# Master.net
KiCad netlist of a schematic drawn in Altium Designer
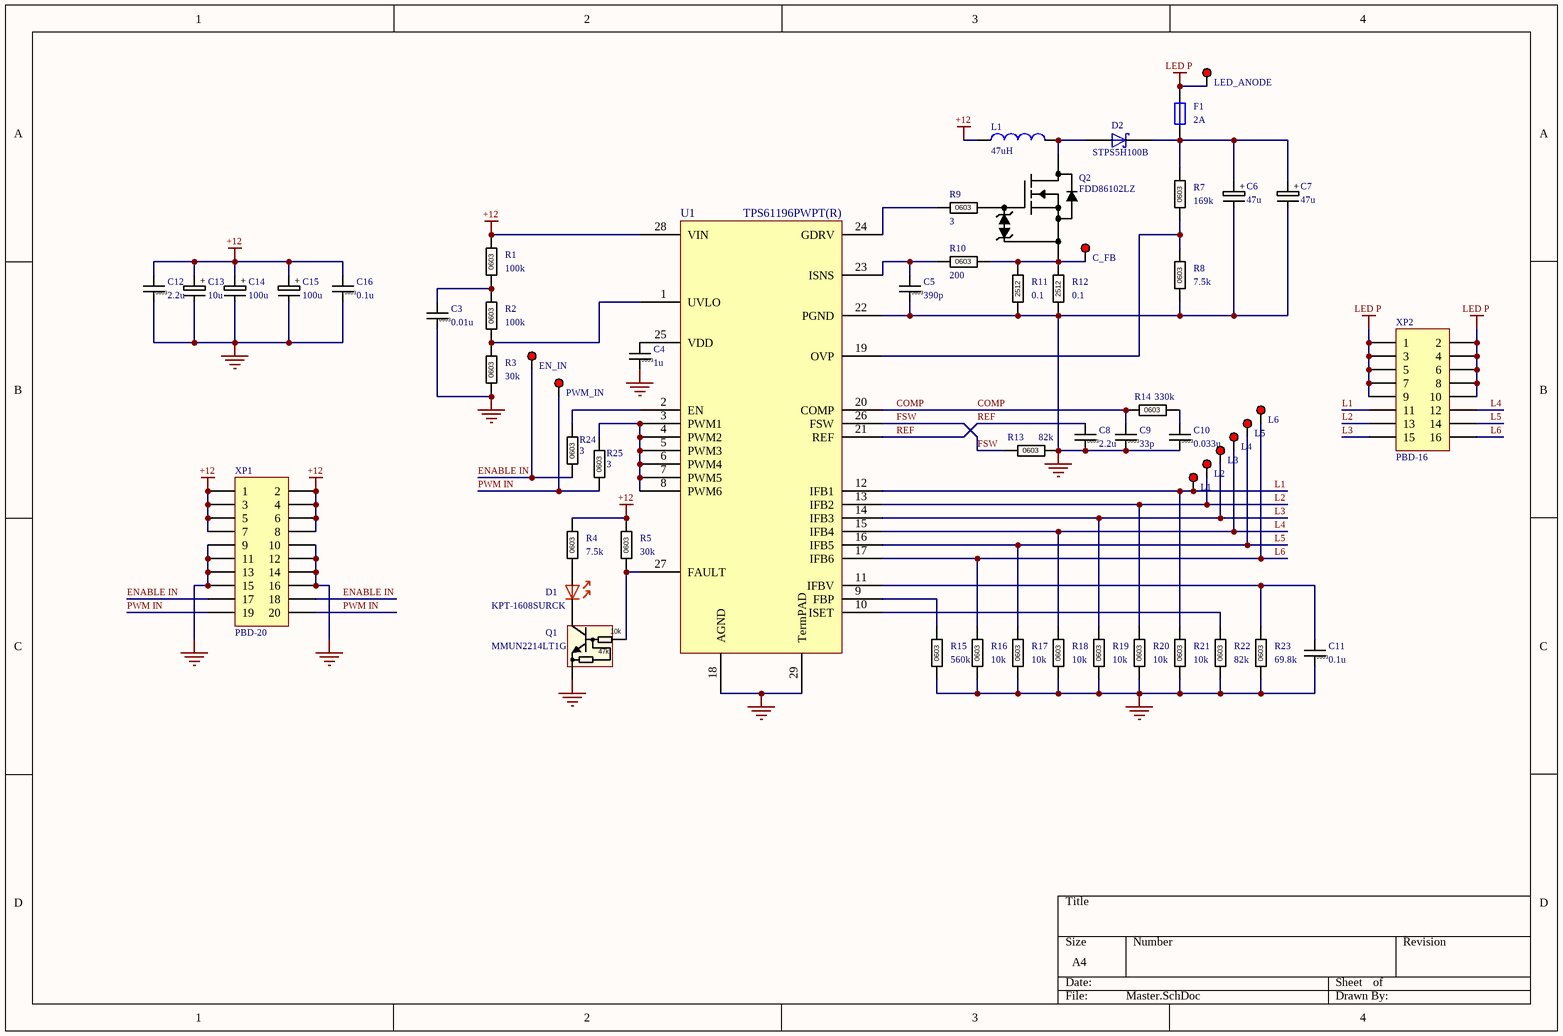
[diagram p0: Master.SchDoc]

(export (version "E")
  (design (tool "Eeschema 10.0.6"))
  (components
    (comp (ref "C3")
      (value "0603-X7R-50-0.01 мкф")
      (footprint "CAP_0603")
      (description "Конденсатор Чип Керамический")
      (fields (field (name "VOLTAGE") "50V") (field (name "CAP") "0.01u") (field (name "FOOT") "0603"))
      (libsource (lib "main") (part "0603-X7R-50-0.01 мкф"))
    )
    (comp (ref "C4")
      (value "0603-X5R-10 1 мкф")
      (footprint "CAP_0603")
      (description "Конденсатор Чип Керамический")
      (fields (field (name "VOLTAGE") "10V") (field (name "CAP") "1u") (field (name "FOOT") "0603"))
      (libsource (lib "main") (part "0603-X5R-10 1 мкф"))
    )
    (comp (ref "C5")
      (value "0603-NP0-50-390 пф J")
      (footprint "CAP_0603")
      (description "Конденсатор Чип Керамический")
      (fields (field (name "VOLTAGE") "50V") (field (name "CAP") "390p") (field (name "FOOT") "0603"))
      (libsource (lib "main") (part "0603-NP0-50-390 пф J"))
    )
    (comp (ref "C6")
      (value "ECAP 47uF 100V 10x12.5")
      (footprint "CAP_ECR 10X12.5")
      (fields (field (name "VOLTAGE") "100V") (field (name "CAP") "47u"))
      (libsource (lib "main") (part "ECAP 47uF 100V 10x12.5"))
    )
    (comp (ref "C7")
      (value "ECAP 47uF 100V 10x12.5")
      (footprint "CAP_ECR 10X12.5")
      (fields (field (name "VOLTAGE") "100V") (field (name "CAP") "47u"))
      (libsource (lib "main") (part "ECAP 47uF 100V 10x12.5"))
    )
    (comp (ref "C8")
      (value "0603-X7R-10 2.2 мкф")
      (footprint "CAP_0603")
      (description "Конденсатор Чип Керамический")
      (fields (field (name "VOLTAGE") "10V") (field (name "CAP") "2.2u") (field (name "FOOT") "0603"))
      (libsource (lib "main") (part "0603-X7R-10 2.2 мкф"))
    )
    (comp (ref "C9")
      (value "0603-NP0-50-33 пф J")
      (footprint "CAP_0603")
      (description "Конденсатор Чип Керамический")
      (fields (field (name "VOLTAGE") "50V") (field (name "CAP") "33p") (field (name "FOOT") "0603"))
      (libsource (lib "main") (part "0603-NP0-50-33 пф J"))
    )
    (comp (ref "C10")
      (value "0603-X7R-50-0.033 мкф")
      (footprint "CAP_0603")
      (description "Конденсатор Чип Керамический")
      (fields (field (name "VOLTAGE") "50V") (field (name "CAP") "0.033u") (field (name "FOOT") "0603"))
      (libsource (lib "main") (part "0603-X7R-50-0.033 мкф"))
    )
    (comp (ref "C11")
      (value "0603-X7R-50-0.1 мкф")
      (footprint "CAP_0603")
      (description "Конденсатор Чип Керамический")
      (fields (field (name "VOLTAGE") "50V") (field (name "CAP") "0.1u") (field (name "FOOT") "0603"))
      (libsource (lib "main") (part "0603-X7R-50-0.1 мкф"))
    )
    (comp (ref "C12")
      (value "0603-X7R-10 2.2 мкф")
      (footprint "CAP_0603")
      (description "Конденсатор Чип Керамический")
      (fields (field (name "VOLTAGE") "10V") (field (name "CAP") "2.2u") (field (name "FOOT") "0603"))
      (libsource (lib "main") (part "0603-X7R-10 2.2 мкф"))
    )
    (comp (ref "C13")
      (value "ESX 50 в-10 мкф 5x11 Hitano")
      (footprint "CAP_ECR 5X11")
      (description "Конденсатор Алюминиевый Низкоимпедансный")
      (fields (field (name "VOLTAGE") "50V") (field (name "CAP") "10u"))
      (libsource (lib "main") (part "ESX 50 в-10 мкф 5x11 Hitano"))
    )
    (comp (ref "C14")
      (value "ECAP (К50-35), 100мкФ, 35В, 105°C, 20%, 6.3x12мм P:2.5мм")
      (footprint "CAP_ECR 5X11")
      (description "Конденсатор электролитический алюминиевый")
      (fields (field (name "VOLTAGE") "50V") (field (name "CAP") "100u"))
      (libsource (lib "main") (part "ECAP 50V 100uF 6.3x12"))
    )
    (comp (ref "C15")
      (value "ECAP (К50-35), 100мкФ, 35В, 105°C, 20%, 6.3x12мм P:2.5мм")
      (footprint "CAP_ECR 5X11")
      (description "Конденсатор электролитический алюминиевый")
      (fields (field (name "VOLTAGE") "50V") (field (name "CAP") "100u"))
      (libsource (lib "main") (part "ECAP 50V 100uF 6.3x12"))
    )
    (comp (ref "C16")
      (value "0603-X7R-50-0.1 мкф")
      (footprint "CAP_0603")
      (description "Конденсатор Чип Керамический")
      (fields (field (name "VOLTAGE") "50V") (field (name "CAP") "0.1u") (field (name "FOOT") "0603"))
      (libsource (lib "main") (part "0603-X7R-50-0.1 мкф"))
    )
    (comp (ref "D1")
      (value "KPT-1608SURCK")
      (footprint "LED_0603_RED")
      (fields
        (field (name "Comment") "KPT-1608SURCK, KingBright")
        (field (name "HELPURL") "L:\\Dev\\Техническая документация\\Светодиоды\\Kingbright\\SMD\\KPT-1608SURCK(0603).pdf")
      )
      (libsource (lib "main") (part "LED_0603_KPT-1608SURCK_red_120mcd"))
    )
    (comp (ref "D2")
      (value "STPS5H100B")
      (footprint "D-PAK")
      (description "DIODE SCHOTTKY 5A 100V")
      (libsource (lib "main") (part "Schottky_STPS5H100B"))
    )
    (comp (ref "F1")
      (value "2A")
      (footprint "FUSE_LITTEL_0154")
      (description "Плавкий предохранитель LITTELFUSE 0154")
      (libsource (lib "main") (part "FUSE_LITTEL 0154"))
    )
    (comp (ref "L1")
      (value "47uH")
      (footprint "INDUCTOR_B82477G")
      (description "47 мкГн, 2.5 А, 12.8х12.8, Катушка индуктивности SMD")
      (libsource (lib "main") (part "INDUCTOR_B82477G4473M"))
    )
    (comp (ref "Q1")
      (value "MMUN2214LT1G")
      (footprint "SOT_23")
      (description "NPN Digital Transistor")
      (fields (field (name "PUBLISHER") "Altium Limited"))
      (libsource (lib "main") (part "BEC_MMUN2214LT1G_50V 0.1A 0.25W"))
    )
    (comp (ref "Q2")
      (value "FDD86102LZ")
      (footprint "D-PAK")
      (description "MOSFET N-CHANNEL 100V 8A")
      (libsource (lib "main") (part "MOSFET_FDD86102LZ"))
    )
    (comp (ref "R1")
      (value "100k")
      (footprint "resistor_0603")
      (description "Резистор Чип")
      (fields
        (field (name "POWER") "0.1W")
        (field (name "FOOT") "0603")
        (field (name "Comment") "0603-100к J")
      )
      (libsource (lib "main") (part "0603-100 к J"))
    )
    (comp (ref "R2")
      (value "100k")
      (footprint "resistor_0603")
      (description "Резистор Чип")
      (fields
        (field (name "POWER") "0.1W")
        (field (name "FOOT") "0603")
        (field (name "Comment") "0603-100к J")
      )
      (libsource (lib "main") (part "0603-100 к J"))
    )
    (comp (ref "R3")
      (value "30k")
      (footprint "resistor_0603")
      (description "Резистор Чип")
      (fields (field (name "POWER") "0.1W") (field (name "TOLERANCE") "1%") (field (name "FOOT") "0603"))
      (libsource (lib "main") (part "0603-30 к F"))
    )
    (comp (ref "R4")
      (value "7.5k")
      (footprint "resistor_0603")
      (description "Резистор Чип")
      (fields (field (name "POWER") "0.1W") (field (name "TOLERANCE") "1%") (field (name "FOOT") "0603"))
      (libsource (lib "main") (part "0603-7.5 к F"))
    )
    (comp (ref "R5")
      (value "30k")
      (footprint "resistor_0603")
      (description "Резистор Чип")
      (fields (field (name "POWER") "0.1W") (field (name "TOLERANCE") "1%") (field (name "FOOT") "0603"))
      (libsource (lib "main") (part "0603-30 к F"))
    )
    (comp (ref "R7")
      (value "169k")
      (footprint "resistor_0603")
      (description "Резистор Чип")
      (fields (field (name "POWER") "0.1W") (field (name "TOLERANCE") "1%") (field (name "FOOT") "0603"))
      (libsource (lib "main") (part "0603-169 к F"))
    )
    (comp (ref "R8")
      (value "7.5k")
      (footprint "resistor_0603")
      (description "Резистор Чип")
      (fields (field (name "POWER") "0.1W") (field (name "TOLERANCE") "1%") (field (name "FOOT") "0603"))
      (libsource (lib "main") (part "0603-7.5 к F"))
    )
    (comp (ref "R9")
      (value "3")
      (footprint "resistor_0603")
      (description "Резистор Чип")
      (fields (field (name "POWER") "0.1W") (field (name "TOLERANCE") "1%") (field (name "FOOT") "0603"))
      (libsource (lib "main") (part "0603-3 F"))
    )
    (comp (ref "R10")
      (value "200")
      (footprint "resistor_0603")
      (description "Резистор Чип")
      (fields (field (name "POWER") "0.1W") (field (name "TOLERANCE") "1%") (field (name "FOOT") "0603"))
      (libsource (lib "main") (part "0603-200 F"))
    )
    (comp (ref "R11")
      (value "0.1")
      (footprint "resistor_2512")
      (description "Резистор Чип")
      (fields (field (name "POWER") "1W") (field (name "FOOT") "2512") (field (name "Comment") "2512-0.1 F"))
      (libsource (lib "main") (part "2512-0.1 F"))
    )
    (comp (ref "R12")
      (value "0.1")
      (footprint "resistor_2512")
      (description "Резистор Чип")
      (fields (field (name "POWER") "1W") (field (name "FOOT") "2512") (field (name "Comment") "2512-0.1 F"))
      (libsource (lib "main") (part "2512-0.1 F"))
    )
    (comp (ref "R13")
      (value "82k")
      (footprint "resistor_0603")
      (description "Резистор Чип")
      (fields
        (field (name "POWER") "0.1W")
        (field (name "FOOT") "0603")
        (field (name "Comment") "0603-82 к J")
      )
      (libsource (lib "main") (part "0603-82 к J"))
    )
    (comp (ref "R14")
      (value "330k")
      (footprint "resistor_0603")
      (description "Резистор Чип")
      (fields
        (field (name "POWER") "0.1W")
        (field (name "FOOT") "0603")
        (field (name "Comment") "0603-330 J")
      )
      (libsource (lib "main") (part "0603-330 J"))
    )
    (comp (ref "R15")
      (value "560k")
      (footprint "resistor_0603")
      (description "Резистор Чип")
      (fields (field (name "POWER") "0.1W") (field (name "TOLERANCE") "1%") (field (name "FOOT") "0603"))
      (libsource (lib "main") (part "0603-560 к F"))
    )
    (comp (ref "R16")
      (value "10k")
      (footprint "resistor_0603")
      (description "Резистор Чип")
      (fields
        (field (name "POWER") "0.1W")
        (field (name "FOOT") "0603")
        (field (name "Comment") "0603-10к J")
      )
      (libsource (lib "main") (part "0603-10 к J"))
    )
    (comp (ref "R17")
      (value "10k")
      (footprint "resistor_0603")
      (description "Резистор Чип")
      (fields
        (field (name "POWER") "0.1W")
        (field (name "FOOT") "0603")
        (field (name "Comment") "0603-10к J")
      )
      (libsource (lib "main") (part "0603-10 к J"))
    )
    (comp (ref "R18")
      (value "10k")
      (footprint "resistor_0603")
      (description "Резистор Чип")
      (fields
        (field (name "POWER") "0.1W")
        (field (name "FOOT") "0603")
        (field (name "Comment") "0603-10к J")
      )
      (libsource (lib "main") (part "0603-10 к J"))
    )
    (comp (ref "R19")
      (value "10k")
      (footprint "resistor_0603")
      (description "Резистор Чип")
      (fields
        (field (name "POWER") "0.1W")
        (field (name "FOOT") "0603")
        (field (name "Comment") "0603-10к J")
      )
      (libsource (lib "main") (part "0603-10 к J"))
    )
    (comp (ref "R20")
      (value "10k")
      (footprint "resistor_0603")
      (description "Резистор Чип")
      (fields
        (field (name "POWER") "0.1W")
        (field (name "FOOT") "0603")
        (field (name "Comment") "0603-10к J")
      )
      (libsource (lib "main") (part "0603-10 к J"))
    )
    (comp (ref "R21")
      (value "10k")
      (footprint "resistor_0603")
      (description "Резистор Чип")
      (fields
        (field (name "POWER") "0.1W")
        (field (name "FOOT") "0603")
        (field (name "Comment") "0603-10к J")
      )
      (libsource (lib "main") (part "0603-10 к J"))
    )
    (comp (ref "R22")
      (value "82k")
      (footprint "resistor_0603")
      (description "Резистор Чип")
      (fields
        (field (name "POWER") "0.1W")
        (field (name "FOOT") "0603")
        (field (name "Comment") "0603-82 к J")
      )
      (libsource (lib "main") (part "0603-82 к J"))
    )
    (comp (ref "R23")
      (value "69.8k")
      (footprint "resistor_0603")
      (description "Резистор Чип")
      (fields (field (name "POWER") "0.1W") (field (name "TOLERANCE") "1%") (field (name "FOOT") "0603"))
      (libsource (lib "main") (part "0603-69.8 к F"))
    )
    (comp (ref "R24")
      (value "3")
      (footprint "resistor_0603")
      (description "Резистор Чип")
      (fields (field (name "POWER") "0.1W") (field (name "TOLERANCE") "1%") (field (name "FOOT") "0603"))
      (libsource (lib "main") (part "0603-3 F"))
    )
    (comp (ref "R25")
      (value "3")
      (footprint "resistor_0603")
      (description "Резистор Чип")
      (fields (field (name "POWER") "0.1W") (field (name "TOLERANCE") "1%") (field (name "FOOT") "0603"))
      (libsource (lib "main") (part "0603-3 F"))
    )
    (comp (ref "TP1")
      (value "LED_ANODE")
      (footprint "OTHER_SMD_TP_1.5MM")
      (libsource (lib "main") (part "Test Point_1.5MM"))
    )
    (comp (ref "TP2")
      (value "EN_IN")
      (footprint "OTHER_SMD_TP_1.5MM")
      (libsource (lib "main") (part "Test Point_1.5MM"))
    )
    (comp (ref "TP3")
      (value "PWM_IN")
      (footprint "OTHER_SMD_TP_1.5MM")
      (libsource (lib "main") (part "Test Point_1.5MM"))
    )
    (comp (ref "TP4")
      (value "L1")
      (footprint "OTHER_SMD_TP_1.5MM")
      (libsource (lib "main") (part "Test Point_1.5MM"))
    )
    (comp (ref "TP5")
      (value "L2")
      (footprint "OTHER_SMD_TP_1.5MM")
      (libsource (lib "main") (part "Test Point_1.5MM"))
    )
    (comp (ref "TP6")
      (value "L3")
      (footprint "OTHER_SMD_TP_1.5MM")
      (libsource (lib "main") (part "Test Point_1.5MM"))
    )
    (comp (ref "TP7")
      (value "L4")
      (footprint "OTHER_SMD_TP_1.5MM")
      (libsource (lib "main") (part "Test Point_1.5MM"))
    )
    (comp (ref "TP8")
      (value "L5")
      (footprint "OTHER_SMD_TP_1.5MM")
      (libsource (lib "main") (part "Test Point_1.5MM"))
    )
    (comp (ref "TP9")
      (value "L6")
      (footprint "OTHER_SMD_TP_1.5MM")
      (libsource (lib "main") (part "Test Point_1.5MM"))
    )
    (comp (ref "TP10")
      (value "C_FB")
      (footprint "OTHER_SMD_TP_1.5MM")
      (libsource (lib "main") (part "Test Point_1.5MM"))
    )
    (comp (ref "U1")
      (value "TPS61196PWPT(R)")
      (footprint "HTSSOP_28")
      (libsource (lib "main") (part "LED DRV_TPS61196"))
    )
    (comp (ref "XP1")
      (value "PBD-20")
      (footprint "CONN_PBD-20")
      (description "Header, 10-Pin, Dual row")
      (fields (field (name "PUBLISHER") "Altium Limited"))
      (libsource (lib "main") (part "CONN_PBD-20"))
    )
    (comp (ref "XP2")
      (value "PBD-16")
      (footprint "CONN_PBD-16")
      (description "Header, 8-Pin, Dual row")
      (fields (field (name "PUBLISHER") "Altium Limited"))
      (libsource (lib "main") (part "CONN_PBD-16"))
    )
  )
  (nets
    (net (code "1") (name "+12") (class "Default")
      (node (ref "C12") (pin "1") (pinfunction "1_1") (pintype "passive"))
      (node (ref "C13") (pin "1") (pinfunction "1_1") (pintype "passive"))
      (node (ref "C14") (pin "1") (pinfunction "1_1") (pintype "passive"))
      (node (ref "C15") (pin "1") (pinfunction "1_1") (pintype "passive"))
      (node (ref "C16") (pin "1") (pinfunction "1_1") (pintype "passive"))
      (node (ref "L1") (pin "1") (pinfunction "1_1") (pintype "passive"))
      (node (ref "R1") (pin "2") (pinfunction "2_2") (pintype "passive"))
      (node (ref "R4") (pin "2") (pinfunction "2_2") (pintype "passive"))
      (node (ref "R5") (pin "2") (pinfunction "2_2") (pintype "passive"))
      (node (ref "U1") (pin "28") (pinfunction "VIN_28") (pintype "passive"))
      (node (ref "XP1") (pin "1") (pinfunction "1_1") (pintype "passive"))
      (node (ref "XP1") (pin "2") (pinfunction "2_2") (pintype "passive"))
      (node (ref "XP1") (pin "3") (pinfunction "3_3") (pintype "passive"))
      (node (ref "XP1") (pin "4") (pinfunction "4_4") (pintype "passive"))
      (node (ref "XP1") (pin "5") (pinfunction "5_5") (pintype "passive"))
      (node (ref "XP1") (pin "6") (pinfunction "6_6") (pintype "passive"))
      (node (ref "XP1") (pin "7") (pinfunction "7_7") (pintype "passive"))
      (node (ref "XP1") (pin "8") (pinfunction "8_8") (pintype "passive"))
    )
    (net (code "2") (name "/COMP") (class "Default")
      (node (ref "C9") (pin "1") (pinfunction "1_1") (pintype "passive"))
      (node (ref "R14") (pin "2") (pinfunction "2_2") (pintype "passive"))
      (node (ref "U1") (pin "20") (pinfunction "COMP_20") (pintype "passive"))
    )
    (net (code "3") (name "/ENABLE IN") (class "Default")
      (node (ref "R24") (pin "1") (pinfunction "1_1") (pintype "passive"))
      (node (ref "TP2") (pin "1") (pinfunction "1_1") (pintype "passive"))
      (node (ref "XP1") (pin "17") (pinfunction "17_17") (pintype "passive"))
      (node (ref "XP1") (pin "18") (pinfunction "18_18") (pintype "passive"))
    )
    (net (code "4") (name "/FSW") (class "Default")
      (node (ref "R13") (pin "1") (pinfunction "1_1") (pintype "passive"))
      (node (ref "U1") (pin "26") (pinfunction "FSW_26") (pintype "passive"))
    )
    (net (code "5") (name "/L1") (class "Default")
      (node (ref "R21") (pin "2") (pinfunction "2_2") (pintype "passive"))
      (node (ref "TP4") (pin "1") (pinfunction "1_1") (pintype "passive"))
      (node (ref "U1") (pin "12") (pinfunction "IFB1_12") (pintype "passive"))
      (node (ref "XP2") (pin "11") (pinfunction "11_11") (pintype "passive"))
    )
    (net (code "6") (name "/L2") (class "Default")
      (node (ref "R20") (pin "2") (pinfunction "2_2") (pintype "passive"))
      (node (ref "TP5") (pin "1") (pinfunction "1_1") (pintype "passive"))
      (node (ref "U1") (pin "13") (pinfunction "IFB2_13") (pintype "passive"))
      (node (ref "XP2") (pin "13") (pinfunction "13_13") (pintype "passive"))
    )
    (net (code "7") (name "/L3") (class "Default")
      (node (ref "R19") (pin "2") (pinfunction "2_2") (pintype "passive"))
      (node (ref "TP6") (pin "1") (pinfunction "1_1") (pintype "passive"))
      (node (ref "U1") (pin "14") (pinfunction "IFB3_14") (pintype "passive"))
      (node (ref "XP2") (pin "15") (pinfunction "15_15") (pintype "passive"))
    )
    (net (code "8") (name "/L4") (class "Default")
      (node (ref "R18") (pin "2") (pinfunction "2_2") (pintype "passive"))
      (node (ref "TP7") (pin "1") (pinfunction "1_1") (pintype "passive"))
      (node (ref "U1") (pin "15") (pinfunction "IFB4_15") (pintype "passive"))
      (node (ref "XP2") (pin "12") (pinfunction "12_12") (pintype "passive"))
    )
    (net (code "9") (name "/L5") (class "Default")
      (node (ref "R17") (pin "2") (pinfunction "2_2") (pintype "passive"))
      (node (ref "TP8") (pin "1") (pinfunction "1_1") (pintype "passive"))
      (node (ref "U1") (pin "16") (pinfunction "IFB5_16") (pintype "passive"))
      (node (ref "XP2") (pin "14") (pinfunction "14_14") (pintype "passive"))
    )
    (net (code "10") (name "/L6") (class "Default")
      (node (ref "R16") (pin "2") (pinfunction "2_2") (pintype "passive"))
      (node (ref "TP9") (pin "1") (pinfunction "1_1") (pintype "passive"))
      (node (ref "U1") (pin "17") (pinfunction "IFB6_17") (pintype "passive"))
      (node (ref "XP2") (pin "16") (pinfunction "16_16") (pintype "passive"))
    )
    (net (code "11") (name "/PWM IN") (class "Default")
      (node (ref "R25") (pin "1") (pinfunction "1_1") (pintype "passive"))
      (node (ref "TP3") (pin "1") (pinfunction "1_1") (pintype "passive"))
      (node (ref "XP1") (pin "19") (pinfunction "19_19") (pintype "passive"))
      (node (ref "XP1") (pin "20") (pinfunction "20_20") (pintype "passive"))
    )
    (net (code "12") (name "/REF") (class "Default")
      (node (ref "C8") (pin "1") (pinfunction "1_1") (pintype "passive"))
      (node (ref "U1") (pin "21") (pinfunction "REF_21") (pintype "passive"))
    )
    (net (code "13") (name "GND") (class "Default")
      (node (ref "C10") (pin "2") (pinfunction "2_2") (pintype "passive"))
      (node (ref "C11") (pin "2") (pinfunction "2_2") (pintype "passive"))
      (node (ref "C12") (pin "2") (pinfunction "2_2") (pintype "passive"))
      (node (ref "C13") (pin "2") (pinfunction "2_2") (pintype "passive"))
      (node (ref "C14") (pin "2") (pinfunction "2_2") (pintype "passive"))
      (node (ref "C15") (pin "2") (pinfunction "2_2") (pintype "passive"))
      (node (ref "C16") (pin "2") (pinfunction "2_2") (pintype "passive"))
      (node (ref "C3") (pin "2") (pinfunction "2_2") (pintype "passive"))
      (node (ref "C4") (pin "2") (pinfunction "2_2") (pintype "passive"))
      (node (ref "C5") (pin "2") (pinfunction "2_2") (pintype "passive"))
      (node (ref "C6") (pin "2") (pinfunction "2_2") (pintype "passive"))
      (node (ref "C7") (pin "2") (pinfunction "2_2") (pintype "passive"))
      (node (ref "C8") (pin "2") (pinfunction "2_2") (pintype "passive"))
      (node (ref "C9") (pin "2") (pinfunction "2_2") (pintype "passive"))
      (node (ref "Q1") (pin "2") (pinfunction "E_2") (pintype "passive"))
      (node (ref "R11") (pin "1") (pinfunction "1_1") (pintype "passive"))
      (node (ref "R12") (pin "1") (pinfunction "1_1") (pintype "passive"))
      (node (ref "R13") (pin "2") (pinfunction "2_2") (pintype "passive"))
      (node (ref "R15") (pin "1") (pinfunction "1_1") (pintype "passive"))
      (node (ref "R16") (pin "1") (pinfunction "1_1") (pintype "passive"))
      (node (ref "R17") (pin "1") (pinfunction "1_1") (pintype "passive"))
      (node (ref "R18") (pin "1") (pinfunction "1_1") (pintype "passive"))
      (node (ref "R19") (pin "1") (pinfunction "1_1") (pintype "passive"))
      (node (ref "R20") (pin "1") (pinfunction "1_1") (pintype "passive"))
      (node (ref "R21") (pin "1") (pinfunction "1_1") (pintype "passive"))
      (node (ref "R22") (pin "1") (pinfunction "1_1") (pintype "passive"))
      (node (ref "R23") (pin "1") (pinfunction "1_1") (pintype "passive"))
      (node (ref "R3") (pin "1") (pinfunction "1_1") (pintype "passive"))
      (node (ref "R8") (pin "1") (pinfunction "1_1") (pintype "passive"))
      (node (ref "U1") (pin "18") (pinfunction "AGND_18") (pintype "passive"))
      (node (ref "U1") (pin "22") (pinfunction "PGND_22") (pintype "passive"))
      (node (ref "U1") (pin "29") (pinfunction "TermPAD_29") (pintype "passive"))
      (node (ref "XP1") (pin "10") (pinfunction "10_10") (pintype "passive"))
      (node (ref "XP1") (pin "11") (pinfunction "11_11") (pintype "passive"))
      (node (ref "XP1") (pin "12") (pinfunction "12_12") (pintype "passive"))
      (node (ref "XP1") (pin "13") (pinfunction "13_13") (pintype "passive"))
      (node (ref "XP1") (pin "14") (pinfunction "14_14") (pintype "passive"))
      (node (ref "XP1") (pin "15") (pinfunction "15_15") (pintype "passive"))
      (node (ref "XP1") (pin "16") (pinfunction "16_16") (pintype "passive"))
      (node (ref "XP1") (pin "9") (pinfunction "9_9") (pintype "passive"))
    )
    (net (code "14") (name "LED P") (class "Default")
      (node (ref "F1") (pin "2") (pinfunction "2_2") (pintype "passive"))
      (node (ref "TP1") (pin "1") (pinfunction "1_1") (pintype "passive"))
      (node (ref "XP2") (pin "1") (pinfunction "1_1") (pintype "passive"))
      (node (ref "XP2") (pin "10") (pinfunction "10_10") (pintype "passive"))
      (node (ref "XP2") (pin "2") (pinfunction "2_2") (pintype "passive"))
      (node (ref "XP2") (pin "3") (pinfunction "3_3") (pintype "passive"))
      (node (ref "XP2") (pin "4") (pinfunction "4_4") (pintype "passive"))
      (node (ref "XP2") (pin "5") (pinfunction "5_5") (pintype "passive"))
      (node (ref "XP2") (pin "6") (pinfunction "6_6") (pintype "passive"))
      (node (ref "XP2") (pin "7") (pinfunction "7_7") (pintype "passive"))
      (node (ref "XP2") (pin "8") (pinfunction "8_8") (pintype "passive"))
      (node (ref "XP2") (pin "9") (pinfunction "9_9") (pintype "passive"))
    )
    (net (code "15") (name "Net-(C3-Pad1)") (class "Default")
      (node (ref "C3") (pin "1") (pinfunction "1_1") (pintype "passive"))
      (node (ref "R1") (pin "1") (pinfunction "1_1") (pintype "passive"))
      (node (ref "R2") (pin "2") (pinfunction "2_2") (pintype "passive"))
    )
    (net (code "16") (name "Net-(C10-Pad1)") (class "Default")
      (node (ref "C10") (pin "1") (pinfunction "1_1") (pintype "passive"))
      (node (ref "R14") (pin "1") (pinfunction "1_1") (pintype "passive"))
    )
    (net (code "17") (name "Net-(D1-Pad1)") (class "Default")
      (node (ref "D1") (pin "1") (pinfunction "1_1") (pintype "passive"))
      (node (ref "R4") (pin "1") (pinfunction "1_1") (pintype "passive"))
    )
    (net (code "18") (name "Net-(D2-A)") (class "Default")
      (node (ref "D2") (pin "2") (pinfunction "A_2") (pintype "passive"))
      (node (ref "L1") (pin "2") (pinfunction "2_2") (pintype "passive"))
      (node (ref "Q2") (pin "3") (pinfunction "D_3") (pintype "passive"))
    )
    (net (code "19") (name "Net-(D2-K)") (class "Default")
      (node (ref "C6") (pin "1") (pinfunction "1_1") (pintype "passive"))
      (node (ref "C7") (pin "1") (pinfunction "1_1") (pintype "passive"))
      (node (ref "D2") (pin "3") (pinfunction "K_3") (pintype "passive"))
      (node (ref "F1") (pin "1") (pinfunction "1_1") (pintype "passive"))
      (node (ref "R7") (pin "2") (pinfunction "2_2") (pintype "passive"))
    )
    (net (code "20") (name "Net-(Q1-B)") (class "Default")
      (node (ref "Q1") (pin "1") (pinfunction "B_1") (pintype "passive"))
      (node (ref "R5") (pin "1") (pinfunction "1_1") (pintype "passive"))
      (node (ref "U1") (pin "27") (pinfunction "FAULT_27") (pintype "passive"))
    )
    (net (code "21") (name "Net-(Q1-C)") (class "Default")
      (node (ref "D1") (pin "2") (pinfunction "2_2") (pintype "passive"))
      (node (ref "Q1") (pin "3") (pinfunction "C_3") (pintype "passive"))
    )
    (net (code "22") (name "Net-(Q2-G)") (class "Default")
      (node (ref "Q2") (pin "1") (pinfunction "G_1") (pintype "passive"))
      (node (ref "R9") (pin "2") (pinfunction "2_2") (pintype "passive"))
    )
    (net (code "23") (name "Net-(Q2-S)") (class "Default")
      (node (ref "Q2") (pin "2") (pinfunction "S_2") (pintype "passive"))
      (node (ref "R10") (pin "2") (pinfunction "2_2") (pintype "passive"))
      (node (ref "R11") (pin "2") (pinfunction "2_2") (pintype "passive"))
      (node (ref "R12") (pin "2") (pinfunction "2_2") (pintype "passive"))
      (node (ref "TP10") (pin "1") (pinfunction "1_1") (pintype "passive"))
    )
    (net (code "24") (name "Net-(U1-EN)") (class "Default")
      (node (ref "R24") (pin "2") (pinfunction "2_2") (pintype "passive"))
      (node (ref "U1") (pin "2") (pinfunction "EN_2") (pintype "passive"))
    )
    (net (code "25") (name "Net-(U1-FBP)") (class "Default")
      (node (ref "R15") (pin "2") (pinfunction "2_2") (pintype "passive"))
      (node (ref "U1") (pin "9") (pinfunction "FBP_9") (pintype "passive"))
    )
    (net (code "26") (name "Net-(U1-GDRV)") (class "Default")
      (node (ref "R9") (pin "1") (pinfunction "1_1") (pintype "passive"))
      (node (ref "U1") (pin "24") (pinfunction "GDRV_24") (pintype "passive"))
    )
    (net (code "27") (name "Net-(U1-IFBV)") (class "Default")
      (node (ref "C11") (pin "1") (pinfunction "1_1") (pintype "passive"))
      (node (ref "R23") (pin "2") (pinfunction "2_2") (pintype "passive"))
      (node (ref "U1") (pin "11") (pinfunction "IFBV_11") (pintype "passive"))
    )
    (net (code "28") (name "Net-(U1-ISET)") (class "Default")
      (node (ref "R22") (pin "2") (pinfunction "2_2") (pintype "passive"))
      (node (ref "U1") (pin "10") (pinfunction "ISET_10") (pintype "passive"))
    )
    (net (code "29") (name "Net-(U1-ISNS)") (class "Default")
      (node (ref "C5") (pin "1") (pinfunction "1_1") (pintype "passive"))
      (node (ref "R10") (pin "1") (pinfunction "1_1") (pintype "passive"))
      (node (ref "U1") (pin "23") (pinfunction "ISNS_23") (pintype "passive"))
    )
    (net (code "30") (name "Net-(U1-OVP)") (class "Default")
      (node (ref "R7") (pin "1") (pinfunction "1_1") (pintype "passive"))
      (node (ref "R8") (pin "2") (pinfunction "2_2") (pintype "passive"))
      (node (ref "U1") (pin "19") (pinfunction "OVP_19") (pintype "passive"))
    )
    (net (code "31") (name "Net-(U1-PWM1)") (class "Default")
      (node (ref "R25") (pin "2") (pinfunction "2_2") (pintype "passive"))
      (node (ref "U1") (pin "3") (pinfunction "PWM1_3") (pintype "passive"))
      (node (ref "U1") (pin "4") (pinfunction "PWM2_4") (pintype "passive"))
      (node (ref "U1") (pin "5") (pinfunction "PWM3_5") (pintype "passive"))
      (node (ref "U1") (pin "6") (pinfunction "PWM4_6") (pintype "passive"))
      (node (ref "U1") (pin "7") (pinfunction "PWM5_7") (pintype "passive"))
      (node (ref "U1") (pin "8") (pinfunction "PWM6_8") (pintype "passive"))
    )
    (net (code "32") (name "Net-(U1-UVLO)") (class "Default")
      (node (ref "R2") (pin "1") (pinfunction "1_1") (pintype "passive"))
      (node (ref "R3") (pin "2") (pinfunction "2_2") (pintype "passive"))
      (node (ref "U1") (pin "1") (pinfunction "UVLO_1") (pintype "passive"))
    )
    (net (code "33") (name "Net-(U1-VDD)") (class "Default")
      (node (ref "C4") (pin "1") (pinfunction "1_1") (pintype "passive"))
      (node (ref "U1") (pin "25") (pinfunction "VDD_25") (pintype "passive"))
    )
  )
)
